# SOM_JB1.net
KiCad netlist of a schematic drawn in Altium Designer
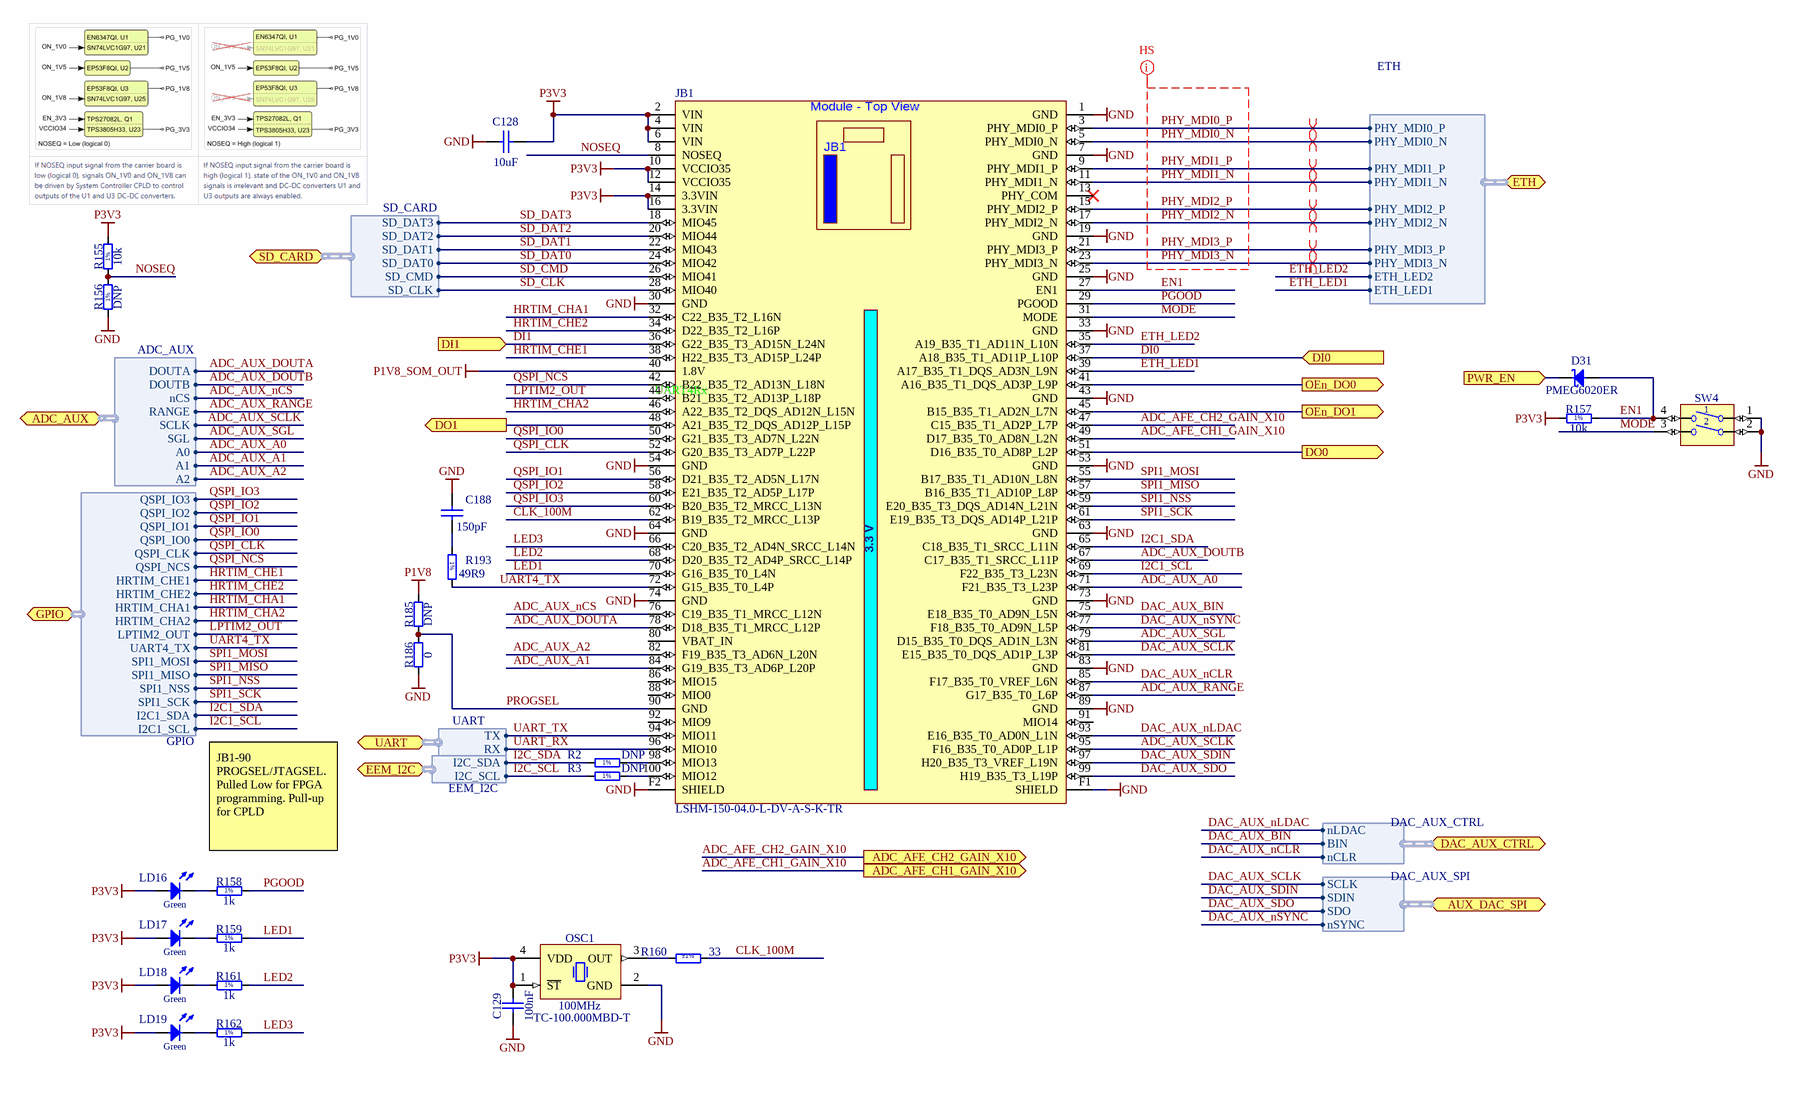
[diagram p0: SOM_JB1.SchDoc]

(export (version "E")
  (design (tool "Eeschema 10.0.6"))
  (components
    (comp (ref "C128")
      (value "10uF")
      (footprint "CAPC1608X80N")
      (description "Non-polarised capacitor")
      (fields
        (field (name "PART NUMBER") "CC0603_10UF_10V_10%_X5R")
        (field (name "VOLTAGE") "10V")
        (field (name "AUTHOR") "CERN DEM JLC")
      )
      (libsource (lib "Capacitors") (part "Capacitor - non polarized"))
    )
    (comp (ref "C129")
      (value "100nF")
      (footprint "CAPC1005X55N")
      (description "Non-polarised capacitor")
      (fields
        (field (name "PART NUMBER") "CC0402_100NF_16V_10%_X5R")
        (field (name "MANUFACTURER") "GENERIC")
        (field (name "AUTHOR") "CERN DEM JLC")
      )
      (libsource (lib "Capacitors") (part "Capacitor - non polarized"))
    )
    (comp (ref "C188")
      (value "150pF")
      (footprint "CAPC1005X55N")
      (description "Non-polarised capacitor")
      (fields
        (field (name "PART NUMBER") "CC0402_150PF_50V_5%_C0G")
        (field (name "VOLTAGE") "50V")
        (field (name "AUTHOR") "CERN DEM JLC")
      )
      (libsource (lib "Capacitors") (part "Capacitor - non polarized"))
    )
    (comp (ref "D31")
      (value "PMEG6020ER")
      (footprint "SODFL3517X110N")
      (description "Schottky Diode")
      (fields
        (field (name "VOLTAGE") "60V")
        (field (name "POWER") "2A")
        (field (name "AUTHOR") "CERN DEM JMW")
      )
      (libsource (lib "ICs And Semiconductors") (part "Diode Schottky"))
    )
    (comp (ref "JB1")
      (value "LSHM-150-04.0-L-DV-A-S-K-TR")
      (footprint "LSHM-150-XXX-X-DV-A-X")
      (description "Samtec Razor Beam REF-189016-02, LF-04.0, 100 Pins, für alle 4x5 SoMs")
      (libsource (lib "SVPX_FMC_6U_SOM") (part "25285"))
    )
    (comp (ref "LD16")
      (value "Green")
      (footprint "LED_KINGBRIGHT_KPH-1608CGCK")
      (description "LED Green 1C 2A")
      (fields
        (field (name "PART NUMBER") "LED_KINGBRIGHT_KPH-1608CGCK")
        (field (name "MANUFACTURER") "KINGBRIGHT")
        (field (name "AUTHOR") "CERN DEM JLC")
      )
      (libsource (lib "ICs And Semiconductors") (part "LED Green 1C 2A"))
    )
    (comp (ref "LD17")
      (value "Green")
      (footprint "LED_KINGBRIGHT_KPH-1608CGCK")
      (description "LED Green 1C 2A")
      (fields
        (field (name "PART NUMBER") "LED_KINGBRIGHT_KPH-1608CGCK")
        (field (name "MANUFACTURER") "KINGBRIGHT")
        (field (name "AUTHOR") "CERN DEM JLC")
      )
      (libsource (lib "ICs And Semiconductors") (part "LED Green 1C 2A"))
    )
    (comp (ref "LD18")
      (value "Green")
      (footprint "LED_KINGBRIGHT_KPH-1608CGCK")
      (description "LED Green 1C 2A")
      (fields
        (field (name "PART NUMBER") "LED_KINGBRIGHT_KPH-1608CGCK")
        (field (name "MANUFACTURER") "KINGBRIGHT")
        (field (name "AUTHOR") "CERN DEM JLC")
      )
      (libsource (lib "ICs And Semiconductors") (part "LED Green 1C 2A"))
    )
    (comp (ref "LD19")
      (value "Green")
      (footprint "LED_KINGBRIGHT_KPH-1608CGCK")
      (description "LED Green 1C 2A")
      (fields
        (field (name "PART NUMBER") "LED_KINGBRIGHT_KPH-1608CGCK")
        (field (name "MANUFACTURER") "KINGBRIGHT")
        (field (name "AUTHOR") "CERN DEM JLC")
      )
      (libsource (lib "ICs And Semiconductors") (part "LED Green 1C 2A"))
    )
    (comp (ref "OSC1")
      (value "100MHz")
      (footprint "OSC_CDFN3225-4LD-PL-1")
      (description "Oscillator MEMS 100MHz ±25ppm")
      (fields
        (field (name "PART NUMBER") "TC-100.000MBD-T")
        (field (name "MANUFACTURER") "TXC")
        (field (name "MANUFACTURER PART NUMBER") "TC-100.000MBD-T")
        (field (name "AUTHOR") "GK")
      )
      (libsource (lib "Crystals_Oscillators") (part "OSC_TC-100.000MBD-T"))
    )
    (comp (ref "R2")
      (value "DNP")
      (footprint "RESC1005X40N")
      (description "Resistor - 1%")
      (fields
        (field (name "PART NUMBER") "R0402_2K4_1%_0.0625W_100PPM")
        (field (name "POWER") "0.0625W")
        (field (name "AUTHOR") "CERN DEM JLC")
      )
      (libsource (lib "Resistors") (part "Resistor - 1%"))
    )
    (comp (ref "R3")
      (value "DNP")
      (footprint "RESC1005X40N")
      (description "Resistor - 1%")
      (fields
        (field (name "PART NUMBER") "R0402_2K4_1%_0.0625W_100PPM")
        (field (name "POWER") "0.0625W")
        (field (name "AUTHOR") "CERN DEM JLC")
      )
      (libsource (lib "Resistors") (part "Resistor - 1%"))
    )
    (comp (ref "R155")
      (value "10k")
      (footprint "RESC1005X40N")
      (description "Resistor - 1%")
      (fields
        (field (name "PART NUMBER") "R0402_10K_1%_0.0625W_100PPM")
        (field (name "MANUFACTURER") "GENERIC")
        (field (name "AUTHOR") "CERN DEM JLC")
      )
      (libsource (lib "Resistors") (part "Resistor - 1%"))
    )
    (comp (ref "R156")
      (value "DNP")
      (footprint "RESC1005X40N")
      (description "Resistor - 1%")
      (fields
        (field (name "PART NUMBER") "R0402_10K_1%_0.0625W_100PPM")
        (field (name "MANUFACTURER") "GENERIC")
        (field (name "AUTHOR") "CERN DEM JLC")
      )
      (libsource (lib "Resistors") (part "Resistor - 1%"))
    )
    (comp (ref "R157")
      (value "10k")
      (footprint "RESC1005X40N")
      (description "Resistor - 1%")
      (fields
        (field (name "PART NUMBER") "R0402_10K_1%_0.0625W_100PPM")
        (field (name "MANUFACTURER") "GENERIC")
        (field (name "AUTHOR") "CERN DEM JLC")
      )
      (libsource (lib "Resistors") (part "Resistor - 1%"))
    )
    (comp (ref "R158")
      (value "1k")
      (footprint "RESC1005X40N")
      (description "Resistor - 1%")
      (fields
        (field (name "PART NUMBER") "R0402_1K_1%_0.0625W_100PPM")
        (field (name "POWER") "0.0625W")
        (field (name "AUTHOR") "CERN DEM JLC")
      )
      (libsource (lib "Resistors") (part "Resistor - 1%"))
    )
    (comp (ref "R159")
      (value "1k")
      (footprint "RESC1005X40N")
      (description "Resistor - 1%")
      (fields
        (field (name "PART NUMBER") "R0402_1K_1%_0.0625W_100PPM")
        (field (name "POWER") "0.0625W")
        (field (name "AUTHOR") "CERN DEM JLC")
      )
      (libsource (lib "Resistors") (part "Resistor - 1%"))
    )
    (comp (ref "R160")
      (value "33")
      (footprint "RESC1005X40N")
      (description "Resistor - 1%")
      (fields
        (field (name "PART NUMBER") "R0402_33R_1%_0.0625W_100PPM")
        (field (name "POWER") "0.0625W")
        (field (name "TOLERANCE") "±1%")
        (field (name "AUTHOR") "CERN DEM JLC")
      )
      (libsource (lib "Resistors") (part "Resistor - 1%"))
    )
    (comp (ref "R161")
      (value "1k")
      (footprint "RESC1005X40N")
      (description "Resistor - 1%")
      (fields
        (field (name "PART NUMBER") "R0402_1K_1%_0.0625W_100PPM")
        (field (name "POWER") "0.0625W")
        (field (name "AUTHOR") "CERN DEM JLC")
      )
      (libsource (lib "Resistors") (part "Resistor - 1%"))
    )
    (comp (ref "R162")
      (value "1k")
      (footprint "RESC1005X40N")
      (description "Resistor - 1%")
      (fields
        (field (name "PART NUMBER") "R0402_1K_1%_0.0625W_100PPM")
        (field (name "POWER") "0.0625W")
        (field (name "AUTHOR") "CERN DEM JLC")
      )
      (libsource (lib "Resistors") (part "Resistor - 1%"))
    )
    (comp (ref "R185")
      (value "DNP")
      (footprint "RESC1005X40N")
      (description "Resistor")
      (fields
        (field (name "PART NUMBER") "R0402_0R_JUMPER")
        (field (name "MANUFACTURER") "GENERIC")
        (field (name "AUTHOR") "CERN DEM JLC")
      )
      (libsource (lib "Resistors") (part "Resistor"))
    )
    (comp (ref "R186")
      (value "0")
      (footprint "RESC1005X40N")
      (description "Resistor")
      (fields
        (field (name "PART NUMBER") "R0402_0R_JUMPER")
        (field (name "MANUFACTURER") "GENERIC")
        (field (name "AUTHOR") "CERN DEM JLC")
      )
      (libsource (lib "Resistors") (part "Resistor"))
    )
    (comp (ref "R193")
      (value "49R9")
      (footprint "RESC1005X40N")
      (description "Resistor - 1%")
      (fields
        (field (name "PART NUMBER") "R0402_49R9_1%_0.0625W_100PPM")
        (field (name "POWER") "0.0625W")
        (field (name "AUTHOR") "CERN DEM JLC")
      )
      (libsource (lib "Resistors") (part "Resistor - 1%"))
    )
    (comp (ref "SW4")
      (value "Switch")
      (footprint "SW_OMRON_A6SN-2101")
      (description "2 Ways SPST DIP Switch")
      (fields
        (field (name "PART NUMBER") "SW_OMRON_A6SN-2101")
        (field (name "MANUFACTURER") "OMRON")
        (field (name "AUTHOR") "CERN DEM MR")
      )
      (libsource (lib "Eletro-mechanical") (part "SW 2x SPST DIP Switch"))
    )
  )
  (nets
    (net (code "9") (name "/ADC_AFE_CH1_GAIN_X10") (class "Default")
      (node (ref "JB1") (pin "49") (pinfunction "D17_B35_T0_AD8N_L2N_49") (pintype "bidirectional"))
    )
    (net (code "10") (name "/ADC_AFE_CH2_GAIN_X10") (class "Default")
      (node (ref "JB1") (pin "47") (pinfunction "C15_B35_T1_AD2P_L7P_47") (pintype "bidirectional"))
    )
    (net (code "11") (name "/ADC_AUX_A0") (class "Default")
      (node (ref "JB1") (pin "71") (pinfunction "F21_B35_T3_L23P_71") (pintype "bidirectional"))
    )
    (net (code "12") (name "/ADC_AUX_A1") (class "Default")
      (node (ref "JB1") (pin "84") (pinfunction "G19_B35_T3_AD6P_L20P_84") (pintype "bidirectional"))
    )
    (net (code "13") (name "/ADC_AUX_A2") (class "Default")
      (node (ref "JB1") (pin "82") (pinfunction "F19_B35_T3_AD6N_L20N_82") (pintype "bidirectional"))
    )
    (net (code "14") (name "/ADC_AUX_DOUTA") (class "Default")
      (node (ref "JB1") (pin "78") (pinfunction "D18_B35_T1_MRCC_L12P_78") (pintype "bidirectional"))
    )
    (net (code "15") (name "/ADC_AUX_DOUTB") (class "Default")
      (node (ref "JB1") (pin "67") (pinfunction "C17_B35_T1_SRCC_L11P_67") (pintype "bidirectional"))
    )
    (net (code "16") (name "/ADC_AUX_RANGE") (class "Default")
      (node (ref "JB1") (pin "87") (pinfunction "G17_B35_T0_L6P_87") (pintype "bidirectional"))
    )
    (net (code "17") (name "/ADC_AUX_SCLK") (class "Default")
      (node (ref "JB1") (pin "95") (pinfunction "F16_B35_T0_AD0P_L1P_95") (pintype "bidirectional"))
    )
    (net (code "18") (name "/ADC_AUX_SGL") (class "Default")
      (node (ref "JB1") (pin "79") (pinfunction "D15_B35_T0_DQS_AD1N_L3N_79") (pintype "bidirectional"))
    )
    (net (code "19") (name "/ADC_AUX_nCS") (class "Default")
      (node (ref "JB1") (pin "76") (pinfunction "C19_B35_T1_MRCC_L12N_76") (pintype "bidirectional"))
    )
    (net (code "20") (name "/CLK_100M") (class "Default")
      (node (ref "JB1") (pin "62") (pinfunction "B19_B35_T2_MRCC_L13P_62") (pintype "bidirectional"))
      (node (ref "R160") (pin "2") (pinfunction "2_2") (pintype "passive"))
    )
    (net (code "21") (name "/DAC_AUX_BIN") (class "Default")
      (node (ref "JB1") (pin "75") (pinfunction "E18_B35_T0_AD9N_L5N_75") (pintype "bidirectional"))
    )
    (net (code "22") (name "/DAC_AUX_SCLK") (class "Default")
      (node (ref "JB1") (pin "81") (pinfunction "E15_B35_T0_DQS_AD1P_L3P_81") (pintype "bidirectional"))
    )
    (net (code "23") (name "/DAC_AUX_SDIN") (class "Default")
      (node (ref "JB1") (pin "97") (pinfunction "H20_B35_T3_VREF_L19N_97") (pintype "bidirectional"))
    )
    (net (code "24") (name "/DAC_AUX_SDO") (class "Default")
      (node (ref "JB1") (pin "99") (pinfunction "H19_B35_T3_L19P_99") (pintype "bidirectional"))
    )
    (net (code "25") (name "/DAC_AUX_nCLR") (class "Default")
      (node (ref "JB1") (pin "85") (pinfunction "F17_B35_T0_VREF_L6N_85") (pintype "bidirectional"))
    )
    (net (code "26") (name "/DAC_AUX_nLDAC") (class "Default")
      (node (ref "JB1") (pin "93") (pinfunction "E16_B35_T0_AD0N_L1N_93") (pintype "bidirectional"))
    )
    (net (code "27") (name "/DAC_AUX_nSYNC") (class "Default")
      (node (ref "JB1") (pin "77") (pinfunction "F18_B35_T0_AD9N_L5P_77") (pintype "bidirectional"))
    )
    (net (code "28") (name "/DI0") (class "Default")
      (node (ref "JB1") (pin "37") (pinfunction "A18_B35_T1_AD11P_L10P_37") (pintype "bidirectional"))
    )
    (net (code "29") (name "/DI1") (class "Default")
      (node (ref "JB1") (pin "36") (pinfunction "G22_B35_T3_AD15N_L24N_36") (pintype "bidirectional"))
    )
    (net (code "30") (name "/DO0") (class "Default")
      (node (ref "JB1") (pin "51") (pinfunction "D16_B35_T0_AD8P_L2P_51") (pintype "bidirectional"))
    )
    (net (code "31") (name "/DO1") (class "Default")
      (node (ref "JB1") (pin "48") (pinfunction "A21_B35_T2_DQS_AD12P_L15P_48") (pintype "bidirectional"))
    )
    (net (code "32") (name "/EN1") (class "Default")
      (node (ref "D31") (pin "2") (pinfunction "A_2") (pintype "passive"))
      (node (ref "JB1") (pin "27") (pinfunction "EN1_27") (pintype "passive"))
      (node (ref "R157") (pin "1") (pinfunction "1_1") (pintype "passive"))
      (node (ref "SW4") (pin "4") (pinfunction "4_4") (pintype "bidirectional"))
    )
    (net (code "33") (name "/ETH_LED1") (class "Default")
      (node (ref "JB1") (pin "39") (pinfunction "A17_B35_T1_DQS_AD3N_L9N_39") (pintype "bidirectional"))
    )
    (net (code "34") (name "/ETH_LED2") (class "Default")
      (node (ref "JB1") (pin "35") (pinfunction "A19_B35_T1_AD11N_L10N_35") (pintype "bidirectional"))
    )
    (net (code "35") (name "/HRTIM_CHA1") (class "Default")
      (node (ref "JB1") (pin "32") (pinfunction "C22_B35_T2_L16N_32") (pintype "bidirectional"))
    )
    (net (code "36") (name "/HRTIM_CHA2") (class "Default")
      (node (ref "JB1") (pin "46") (pinfunction "A22_B35_T2_DQS_AD12N_L15N_46") (pintype "bidirectional"))
    )
    (net (code "37") (name "/HRTIM_CHE1") (class "Default")
      (node (ref "JB1") (pin "38") (pinfunction "H22_B35_T3_AD15P_L24P_38") (pintype "bidirectional"))
    )
    (net (code "38") (name "/HRTIM_CHE2") (class "Default")
      (node (ref "JB1") (pin "34") (pinfunction "D22_B35_T2_L16P_34") (pintype "bidirectional"))
    )
    (net (code "39") (name "/I2C1_SCL") (class "Default")
      (node (ref "JB1") (pin "69") (pinfunction "F22_B35_T3_L23N_69") (pintype "bidirectional"))
    )
    (net (code "40") (name "/I2C1_SDA") (class "Default")
      (node (ref "JB1") (pin "65") (pinfunction "C18_B35_T1_SRCC_L11N_65") (pintype "bidirectional"))
    )
    (net (code "41") (name "/I2C_SCL") (class "Default")
      (node (ref "R3") (pin "1") (pinfunction "1_1") (pintype "passive"))
    )
    (net (code "42") (name "/I2C_SDA") (class "Default")
      (node (ref "R2") (pin "1") (pinfunction "1_1") (pintype "passive"))
    )
    (net (code "43") (name "/LED1") (class "Default")
      (node (ref "JB1") (pin "70") (pinfunction "G16_B35_T0_L4N_70") (pintype "bidirectional"))
      (node (ref "R159") (pin "2") (pinfunction "2_2") (pintype "passive"))
    )
    (net (code "44") (name "/LED2") (class "Default")
      (node (ref "JB1") (pin "68") (pinfunction "D20_B35_T2_AD4P_SRCC_L14P_68") (pintype "bidirectional"))
      (node (ref "R161") (pin "2") (pinfunction "2_2") (pintype "passive"))
    )
    (net (code "45") (name "/LED3") (class "Default")
      (node (ref "JB1") (pin "66") (pinfunction "C20_B35_T2_AD4N_SRCC_L14N_66") (pintype "bidirectional"))
      (node (ref "R162") (pin "2") (pinfunction "2_2") (pintype "passive"))
    )
    (net (code "46") (name "/LPTIM2_OUT") (class "Default")
      (node (ref "JB1") (pin "44") (pinfunction "B21_B35_T2_AD13P_L18P_44") (pintype "bidirectional"))
    )
    (net (code "47") (name "/MODE") (class "Default")
      (node (ref "JB1") (pin "31") (pinfunction "MODE_31") (pintype "passive"))
      (node (ref "SW4") (pin "3") (pinfunction "3_3") (pintype "bidirectional"))
    )
    (net (code "48") (name "/NOSEQ") (class "Default")
      (node (ref "JB1") (pin "8") (pinfunction "NOSEQ_8") (pintype "passive"))
      (node (ref "R155") (pin "1") (pinfunction "1_1") (pintype "passive"))
      (node (ref "R156") (pin "2") (pinfunction "2_2") (pintype "passive"))
    )
    (net (code "49") (name "/OEn_DO0") (class "Default")
      (node (ref "JB1") (pin "41") (pinfunction "A16_B35_T1_DQS_AD3P_L9P_41") (pintype "bidirectional"))
    )
    (net (code "50") (name "/OEn_DO1") (class "Default")
      (node (ref "JB1") (pin "45") (pinfunction "B15_B35_T1_AD2N_L7N_45") (pintype "bidirectional"))
    )
    (net (code "51") (name "/PGOOD") (class "Default")
      (node (ref "JB1") (pin "29") (pinfunction "PGOOD_29") (pintype "passive"))
      (node (ref "R158") (pin "2") (pinfunction "2_2") (pintype "passive"))
    )
    (net (code "52") (name "/PHY_MDI0_N") (class "Default")
      (node (ref "JB1") (pin "5") (pinfunction "PHY_MDI0_N_5") (pintype "bidirectional"))
    )
    (net (code "53") (name "/PHY_MDI0_P") (class "Default")
      (node (ref "JB1") (pin "3") (pinfunction "PHY_MDI0_P_3") (pintype "bidirectional"))
    )
    (net (code "54") (name "/PHY_MDI1_N") (class "Default")
      (node (ref "JB1") (pin "11") (pinfunction "PHY_MDI1_N_11") (pintype "bidirectional"))
    )
    (net (code "55") (name "/PHY_MDI1_P") (class "Default")
      (node (ref "JB1") (pin "9") (pinfunction "PHY_MDI1_P_9") (pintype "bidirectional"))
    )
    (net (code "56") (name "/PHY_MDI2_N") (class "Default")
      (node (ref "JB1") (pin "17") (pinfunction "PHY_MDI2_N_17") (pintype "bidirectional"))
    )
    (net (code "57") (name "/PHY_MDI2_P") (class "Default")
      (node (ref "JB1") (pin "15") (pinfunction "PHY_MDI2_P_15") (pintype "bidirectional"))
    )
    (net (code "58") (name "/PHY_MDI3_N") (class "Default")
      (node (ref "JB1") (pin "23") (pinfunction "PHY_MDI3_N_23") (pintype "bidirectional"))
    )
    (net (code "59") (name "/PHY_MDI3_P") (class "Default")
      (node (ref "JB1") (pin "21") (pinfunction "PHY_MDI3_P_21") (pintype "bidirectional"))
    )
    (net (code "60") (name "/PROGSEL") (class "Default")
      (node (ref "JB1") (pin "90") (pinfunction "GND_90") (pintype "power_in"))
      (node (ref "R185") (pin "1") (pinfunction "1_1") (pintype "passive"))
      (node (ref "R186") (pin "2") (pinfunction "2_2") (pintype "passive"))
    )
    (net (code "61") (name "/PWR_EN") (class "Default")
      (node (ref "D31") (pin "1") (pinfunction "C_1") (pintype "passive"))
    )
    (net (code "62") (name "/QSPI_CLK") (class "Default")
      (node (ref "JB1") (pin "52") (pinfunction "G20_B35_T3_AD7P_L22P_52") (pintype "bidirectional"))
    )
    (net (code "63") (name "/QSPI_IO0") (class "Default")
      (node (ref "JB1") (pin "50") (pinfunction "G21_B35_T3_AD7N_L22N_50") (pintype "bidirectional"))
    )
    (net (code "64") (name "/QSPI_IO1") (class "Default")
      (node (ref "JB1") (pin "56") (pinfunction "D21_B35_T2_AD5N_L17N_56") (pintype "bidirectional"))
    )
    (net (code "65") (name "/QSPI_IO2") (class "Default")
      (node (ref "JB1") (pin "58") (pinfunction "E21_B35_T2_AD5P_L17P_58") (pintype "bidirectional"))
    )
    (net (code "66") (name "/QSPI_IO3") (class "Default")
      (node (ref "JB1") (pin "60") (pinfunction "B20_B35_T2_MRCC_L13N_60") (pintype "bidirectional"))
    )
    (net (code "67") (name "/QSPI_NCS") (class "Default")
      (node (ref "JB1") (pin "42") (pinfunction "B22_B35_T2_AD13N_L18N_42") (pintype "bidirectional"))
    )
    (net (code "68") (name "/SD_CLK") (class "Default")
      (node (ref "JB1") (pin "28") (pinfunction "MIO40_28") (pintype "bidirectional"))
    )
    (net (code "69") (name "/SD_CMD") (class "Default")
      (node (ref "JB1") (pin "26") (pinfunction "MIO41_26") (pintype "bidirectional"))
    )
    (net (code "70") (name "/SD_DAT0") (class "Default")
      (node (ref "JB1") (pin "24") (pinfunction "MIO42_24") (pintype "bidirectional"))
    )
    (net (code "71") (name "/SD_DAT1") (class "Default")
      (node (ref "JB1") (pin "22") (pinfunction "MIO43_22") (pintype "bidirectional"))
    )
    (net (code "72") (name "/SD_DAT2") (class "Default")
      (node (ref "JB1") (pin "20") (pinfunction "MIO44_20") (pintype "bidirectional"))
    )
    (net (code "73") (name "/SD_DAT3") (class "Default")
      (node (ref "JB1") (pin "18") (pinfunction "MIO45_18") (pintype "bidirectional"))
    )
    (net (code "74") (name "/SPI1_MISO") (class "Default")
      (node (ref "JB1") (pin "57") (pinfunction "B16_B35_T1_AD10P_L8P_57") (pintype "bidirectional"))
    )
    (net (code "75") (name "/SPI1_MOSI") (class "Default")
      (node (ref "JB1") (pin "55") (pinfunction "B17_B35_T1_AD10N_L8N_55") (pintype "bidirectional"))
    )
    (net (code "76") (name "/SPI1_NSS") (class "Default")
      (node (ref "JB1") (pin "59") (pinfunction "E20_B35_T3_DQS_AD14N_L21N_59") (pintype "bidirectional"))
    )
    (net (code "77") (name "/SPI1_SCK") (class "Default")
      (node (ref "JB1") (pin "61") (pinfunction "E19_B35_T3_DQS_AD14P_L21P_61") (pintype "bidirectional"))
    )
    (net (code "78") (name "/UART4_TX") (class "Default")
      (node (ref "JB1") (pin "72") (pinfunction "G15_B35_T0_L4P_72") (pintype "bidirectional"))
      (node (ref "R193") (pin "2") (pinfunction "2_2") (pintype "passive"))
    )
    (net (code "79") (name "/UART_RX") (class "Default")
      (node (ref "JB1") (pin "96") (pinfunction "MIO10_96") (pintype "bidirectional"))
    )
    (net (code "80") (name "/UART_TX") (class "Default")
      (node (ref "JB1") (pin "94") (pinfunction "MIO11_94") (pintype "bidirectional"))
    )
    (net (code "89") (name "GND") (class "Default")
      (node (ref "C128") (pin "2") (pinfunction "2_2") (pintype "passive"))
      (node (ref "C129") (pin "1") (pinfunction "1_1") (pintype "passive"))
      (node (ref "C188") (pin "2") (pinfunction "2_2") (pintype "passive"))
      (node (ref "JB1") (pin "1") (pinfunction "GND_1") (pintype "power_in"))
      (node (ref "JB1") (pin "19") (pinfunction "GND_19") (pintype "power_in"))
      (node (ref "JB1") (pin "25") (pinfunction "GND_25") (pintype "power_in"))
      (node (ref "JB1") (pin "30") (pinfunction "GND_30") (pintype "power_in"))
      (node (ref "JB1") (pin "33") (pinfunction "GND_33") (pintype "power_in"))
      (node (ref "JB1") (pin "43") (pinfunction "GND_43") (pintype "power_in"))
      (node (ref "JB1") (pin "53") (pinfunction "GND_53") (pintype "power_in"))
      (node (ref "JB1") (pin "54") (pinfunction "GND_54") (pintype "power_in"))
      (node (ref "JB1") (pin "63") (pinfunction "GND_63") (pintype "power_in"))
      (node (ref "JB1") (pin "64") (pinfunction "GND_64") (pintype "power_in"))
      (node (ref "JB1") (pin "7") (pinfunction "GND_7") (pintype "power_in"))
      (node (ref "JB1") (pin "73") (pinfunction "GND_73") (pintype "power_in"))
      (node (ref "JB1") (pin "74") (pinfunction "GND_74") (pintype "power_in"))
      (node (ref "JB1") (pin "83") (pinfunction "GND_83") (pintype "power_in"))
      (node (ref "JB1") (pin "89") (pinfunction "GND_89") (pintype "power_in"))
      (node (ref "JB1") (pin "F1") (pinfunction "SHIELD_F1") (pintype "power_in"))
      (node (ref "JB1") (pin "F2") (pinfunction "SHIELD_F2") (pintype "power_in"))
      (node (ref "OSC1") (pin "2") (pinfunction "GND_2") (pintype "power_in"))
      (node (ref "R156") (pin "1") (pinfunction "1_1") (pintype "passive"))
      (node (ref "R186") (pin "1") (pinfunction "1_1") (pintype "passive"))
      (node (ref "SW4") (pin "1") (pinfunction "1_1") (pintype "bidirectional"))
      (node (ref "SW4") (pin "2") (pinfunction "2_2") (pintype "bidirectional"))
    )
    (net (code "90") (name "Net-(C188-Pad1)") (class "Default")
      (node (ref "C188") (pin "1") (pinfunction "1_1") (pintype "passive"))
      (node (ref "R193") (pin "1") (pinfunction "1_1") (pintype "passive"))
    )
    (net (code "91") (name "Net-(JB1-MIO12)") (class "Default")
      (node (ref "JB1") (pin "100") (pinfunction "MIO12_100") (pintype "bidirectional"))
      (node (ref "R3") (pin "2") (pinfunction "2_2") (pintype "passive"))
    )
    (net (code "92") (name "Net-(JB1-MIO13)") (class "Default")
      (node (ref "JB1") (pin "98") (pinfunction "MIO13_98") (pintype "bidirectional"))
      (node (ref "R2") (pin "2") (pinfunction "2_2") (pintype "passive"))
    )
    (net (code "93") (name "Net-(LD16-C)") (class "Default")
      (node (ref "LD16") (pin "1") (pinfunction "C_1") (pintype "passive"))
      (node (ref "R158") (pin "1") (pinfunction "1_1") (pintype "passive"))
    )
    (net (code "94") (name "Net-(LD17-C)") (class "Default")
      (node (ref "LD17") (pin "1") (pinfunction "C_1") (pintype "passive"))
      (node (ref "R159") (pin "1") (pinfunction "1_1") (pintype "passive"))
    )
    (net (code "95") (name "Net-(LD18-C)") (class "Default")
      (node (ref "LD18") (pin "1") (pinfunction "C_1") (pintype "passive"))
      (node (ref "R161") (pin "1") (pinfunction "1_1") (pintype "passive"))
    )
    (net (code "96") (name "Net-(LD19-C)") (class "Default")
      (node (ref "LD19") (pin "1") (pinfunction "C_1") (pintype "passive"))
      (node (ref "R162") (pin "1") (pinfunction "1_1") (pintype "passive"))
    )
    (net (code "97") (name "Net-(OSC1-OUT)") (class "Default")
      (node (ref "OSC1") (pin "3") (pinfunction "OUT_3") (pintype "output"))
      (node (ref "R160") (pin "1") (pinfunction "1_1") (pintype "passive"))
    )
    (net (code "98") (name "P1V8") (class "Default")
      (node (ref "R185") (pin "2") (pinfunction "2_2") (pintype "passive"))
    )
    (net (code "99") (name "P1V8_SOM_OUT") (class "Default")
      (node (ref "JB1") (pin "40") (pinfunction "1.8V_40") (pintype "power_in"))
    )
    (net (code "100") (name "P3V3") (class "Default")
      (node (ref "C128") (pin "1") (pinfunction "1_1") (pintype "passive"))
      (node (ref "C129") (pin "2") (pinfunction "2_2") (pintype "passive"))
      (node (ref "JB1") (pin "10") (pinfunction "VCCIO35_10") (pintype "power_in"))
      (node (ref "JB1") (pin "12") (pinfunction "VCCIO35_12") (pintype "power_in"))
      (node (ref "JB1") (pin "14") (pinfunction "3.3VIN_14") (pintype "power_in"))
      (node (ref "JB1") (pin "16") (pinfunction "3.3VIN_16") (pintype "power_in"))
      (node (ref "JB1") (pin "2") (pinfunction "VIN_2") (pintype "power_in"))
      (node (ref "JB1") (pin "4") (pinfunction "VIN_4") (pintype "power_in"))
      (node (ref "JB1") (pin "6") (pinfunction "VIN_6") (pintype "power_in"))
      (node (ref "LD16") (pin "2") (pinfunction "A_2") (pintype "passive"))
      (node (ref "LD17") (pin "2") (pinfunction "A_2") (pintype "passive"))
      (node (ref "LD18") (pin "2") (pinfunction "A_2") (pintype "passive"))
      (node (ref "LD19") (pin "2") (pinfunction "A_2") (pintype "passive"))
      (node (ref "OSC1") (pin "1") (pinfunction "~{ST}_1") (pintype "input"))
      (node (ref "OSC1") (pin "4") (pinfunction "VDD_4") (pintype "power_in"))
      (node (ref "R155") (pin "2") (pinfunction "2_2") (pintype "passive"))
      (node (ref "R157") (pin "2") (pinfunction "2_2") (pintype "passive"))
    )
    (net (code "101") (name "unconnected-(JB1-MIO0-Pad88)") (class "Default")
      (node (ref "JB1") (pin "88") (pinfunction "MIO0_88") (pintype "bidirectional"))
    )
    (net (code "102") (name "unconnected-(JB1-MIO9-Pad92)") (class "Default")
      (node (ref "JB1") (pin "92") (pinfunction "MIO9_92") (pintype "bidirectional"))
    )
    (net (code "103") (name "unconnected-(JB1-MIO14-Pad91)") (class "Default")
      (node (ref "JB1") (pin "91") (pinfunction "MIO14_91") (pintype "bidirectional"))
    )
    (net (code "104") (name "unconnected-(JB1-MIO15-Pad86)") (class "Default")
      (node (ref "JB1") (pin "86") (pinfunction "MIO15_86") (pintype "bidirectional"))
    )
    (net (code "105") (name "unconnected-(JB1-PHY_COM-Pad13)") (class "Default")
      (node (ref "JB1") (pin "13") (pinfunction "PHY_COM_13") (pintype "passive+no_connect"))
    )
    (net (code "106") (name "unconnected-(JB1-VBAT_IN-Pad80)") (class "Default")
      (node (ref "JB1") (pin "80") (pinfunction "VBAT_IN_80") (pintype "power_in"))
    )
  )
)
